# ZYNQ400-CONDIP.net
KiCad netlist of a schematic drawn in Altium Designer
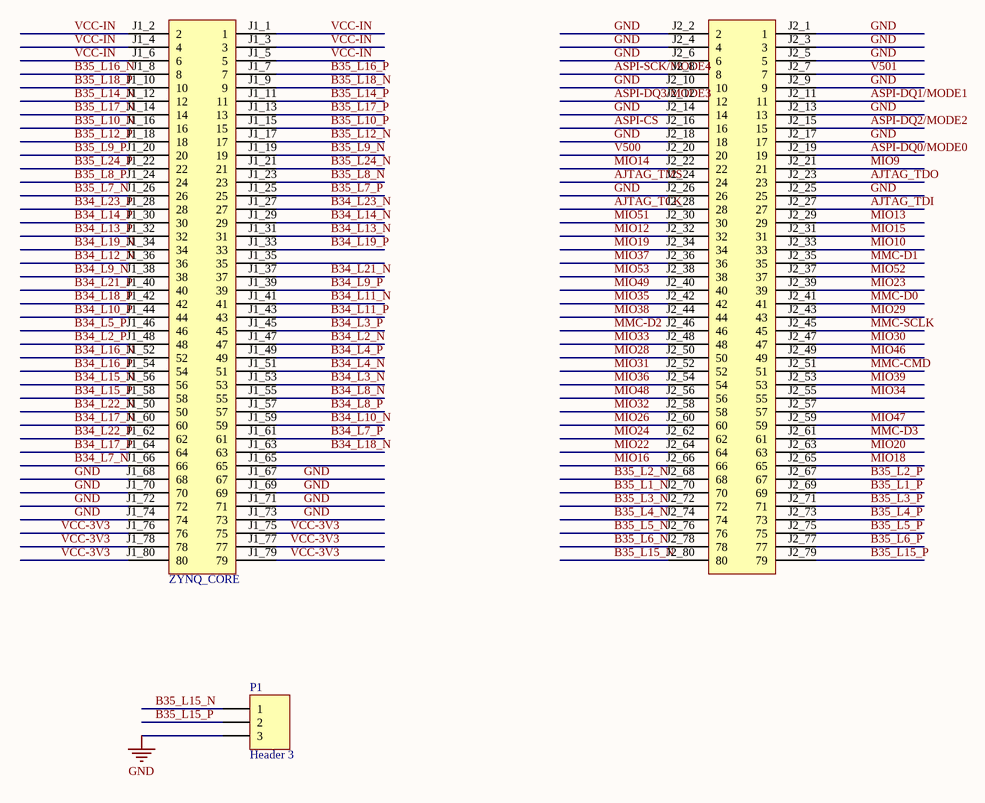
[diagram p0: ZYNQ400-CONDIP.SchDoc]

(export (version "E")
  (design (tool "Eeschema 10.0.6"))
  (components
    (comp (ref "M1")
      (value "ZYNQ_CORE")
      (footprint "ZYNQ7010&7020")
      (description "ZYNQ7010&7020 Core Board")
      (libsource (lib "ZYNQ领航者底板") (part "ZYNQ7010&7020"))
    )
    (comp (ref "P1")
      (value "Header 3")
      (footprint "HDR1X3")
      (description "Header, 3-Pin")
      (fields (field (name "PUBLISHER") "Altium Limited"))
      (libsource (lib "Miscellaneous Connectors") (part "Header 3"))
    )
  )
  (nets
    (net (code "1") (name "/AJTAG_TCK") (class "Default")
      (node (ref "M1") (pin "J2_28") (pinfunction "28_J2_28") (pintype "passive"))
    )
    (net (code "2") (name "/AJTAG_TDI") (class "Default")
      (node (ref "M1") (pin "J2_27") (pinfunction "27_J2_27") (pintype "passive"))
    )
    (net (code "3") (name "/AJTAG_TDO") (class "Default")
      (node (ref "M1") (pin "J2_23") (pinfunction "23_J2_23") (pintype "passive"))
    )
    (net (code "4") (name "/AJTAG_TMS") (class "Default")
      (node (ref "M1") (pin "J2_24") (pinfunction "24_J2_24") (pintype "passive"))
    )
    (net (code "5") (name "/ASPI-CS") (class "Default")
      (node (ref "M1") (pin "J2_16") (pinfunction "16_J2_16") (pintype "passive"))
    )
    (net (code "6") (name "/ASPI-DQ0{slash}MODE0") (class "Default")
      (node (ref "M1") (pin "J2_19") (pinfunction "19_J2_19") (pintype "passive"))
    )
    (net (code "7") (name "/ASPI-DQ1{slash}MODE1") (class "Default")
      (node (ref "M1") (pin "J2_11") (pinfunction "11_J2_11") (pintype "passive"))
    )
    (net (code "8") (name "/ASPI-DQ2{slash}MODE2") (class "Default")
      (node (ref "M1") (pin "J2_15") (pinfunction "15_J2_15") (pintype "passive"))
    )
    (net (code "9") (name "/ASPI-DQ3{slash}MODE3") (class "Default")
      (node (ref "M1") (pin "J2_12") (pinfunction "12_J2_12") (pintype "passive"))
    )
    (net (code "10") (name "/ASPI-SCK{slash}MODE4") (class "Default")
      (node (ref "M1") (pin "J2_8") (pinfunction "8_J2_8") (pintype "passive"))
    )
    (net (code "11") (name "/B34_L2_N") (class "Default")
      (node (ref "M1") (pin "J1_47") (pinfunction "47_J1_47") (pintype "passive"))
    )
    (net (code "12") (name "/B34_L2_P") (class "Default")
      (node (ref "M1") (pin "J1_48") (pinfunction "48_J1_48") (pintype "passive"))
    )
    (net (code "13") (name "/B34_L3_N") (class "Default")
      (node (ref "M1") (pin "J1_53") (pinfunction "53_J1_53") (pintype "passive"))
    )
    (net (code "14") (name "/B34_L3_P") (class "Default")
      (node (ref "M1") (pin "J1_45") (pinfunction "45_J1_45") (pintype "passive"))
    )
    (net (code "15") (name "/B34_L4_N") (class "Default")
      (node (ref "M1") (pin "J1_51") (pinfunction "51_J1_51") (pintype "passive"))
    )
    (net (code "16") (name "/B34_L4_P") (class "Default")
      (node (ref "M1") (pin "J1_49") (pinfunction "49_J1_49") (pintype "passive"))
    )
    (net (code "17") (name "/B34_L5_P") (class "Default")
      (node (ref "M1") (pin "J1_46") (pinfunction "46_J1_46") (pintype "passive"))
    )
    (net (code "18") (name "/B34_L7_N") (class "Default")
      (node (ref "M1") (pin "J1_66") (pinfunction "66_J1_66") (pintype "passive"))
    )
    (net (code "19") (name "/B34_L7_P") (class "Default")
      (node (ref "M1") (pin "J1_61") (pinfunction "61_J1_61") (pintype "passive"))
    )
    (net (code "20") (name "/B34_L8_N") (class "Default")
      (node (ref "M1") (pin "J1_55") (pinfunction "55_J1_55") (pintype "passive"))
    )
    (net (code "21") (name "/B34_L8_P") (class "Default")
      (node (ref "M1") (pin "J1_57") (pinfunction "57_J1_57") (pintype "passive"))
    )
    (net (code "22") (name "/B34_L9_N") (class "Default")
      (node (ref "M1") (pin "J1_38") (pinfunction "38_J1_38") (pintype "passive"))
    )
    (net (code "23") (name "/B34_L9_P") (class "Default")
      (node (ref "M1") (pin "J1_39") (pinfunction "39_J1_39") (pintype "passive"))
    )
    (net (code "24") (name "/B34_L10_N") (class "Default")
      (node (ref "M1") (pin "J1_59") (pinfunction "59_J1_59") (pintype "passive"))
    )
    (net (code "25") (name "/B34_L10_P") (class "Default")
      (node (ref "M1") (pin "J1_44") (pinfunction "44_J1_44") (pintype "passive"))
    )
    (net (code "26") (name "/B34_L11_N") (class "Default")
      (node (ref "M1") (pin "J1_41") (pinfunction "41_J1_41") (pintype "passive"))
    )
    (net (code "27") (name "/B34_L11_P") (class "Default")
      (node (ref "M1") (pin "J1_43") (pinfunction "43_J1_43") (pintype "passive"))
    )
    (net (code "28") (name "/B34_L12_N") (class "Default")
      (node (ref "M1") (pin "J1_36") (pinfunction "36_J1_36") (pintype "passive"))
    )
    (net (code "29") (name "/B34_L13_N") (class "Default")
      (node (ref "M1") (pin "J1_31") (pinfunction "31_J1_31") (pintype "passive"))
    )
    (net (code "30") (name "/B34_L13_P") (class "Default")
      (node (ref "M1") (pin "J1_32") (pinfunction "32_J1_32") (pintype "passive"))
    )
    (net (code "31") (name "/B34_L14_N") (class "Default")
      (node (ref "M1") (pin "J1_29") (pinfunction "29_J1_29") (pintype "passive"))
    )
    (net (code "32") (name "/B34_L14_P") (class "Default")
      (node (ref "M1") (pin "J1_30") (pinfunction "30_J1_30") (pintype "passive"))
    )
    (net (code "33") (name "/B34_L15_N") (class "Default")
      (node (ref "M1") (pin "J1_56") (pinfunction "56_J1_56") (pintype "passive"))
    )
    (net (code "34") (name "/B34_L15_P") (class "Default")
      (node (ref "M1") (pin "J1_58") (pinfunction "58_J1_58") (pintype "passive"))
    )
    (net (code "35") (name "/B34_L16_N") (class "Default")
      (node (ref "M1") (pin "J1_52") (pinfunction "52_J1_52") (pintype "passive"))
    )
    (net (code "36") (name "/B34_L16_P") (class "Default")
      (node (ref "M1") (pin "J1_54") (pinfunction "54_J1_54") (pintype "passive"))
    )
    (net (code "37") (name "/B34_L17_N") (class "Default")
      (node (ref "M1") (pin "J1_60") (pinfunction "60_J1_60") (pintype "passive"))
    )
    (net (code "38") (name "/B34_L17_P") (class "Default")
      (node (ref "M1") (pin "J1_64") (pinfunction "64_J1_64") (pintype "passive"))
    )
    (net (code "39") (name "/B34_L18_N") (class "Default")
      (node (ref "M1") (pin "J1_63") (pinfunction "63_J1_63") (pintype "passive"))
    )
    (net (code "40") (name "/B34_L18_P") (class "Default")
      (node (ref "M1") (pin "J1_42") (pinfunction "42_J1_42") (pintype "passive"))
    )
    (net (code "41") (name "/B34_L19_N") (class "Default")
      (node (ref "M1") (pin "J1_34") (pinfunction "34_J1_34") (pintype "passive"))
    )
    (net (code "42") (name "/B34_L19_P") (class "Default")
      (node (ref "M1") (pin "J1_33") (pinfunction "33_J1_33") (pintype "passive"))
    )
    (net (code "43") (name "/B34_L21_N") (class "Default")
      (node (ref "M1") (pin "J1_37") (pinfunction "37_J1_37") (pintype "passive"))
    )
    (net (code "44") (name "/B34_L21_P") (class "Default")
      (node (ref "M1") (pin "J1_40") (pinfunction "40_J1_40") (pintype "passive"))
    )
    (net (code "45") (name "/B34_L22_N") (class "Default")
      (node (ref "M1") (pin "J1_50") (pinfunction "50_J1_50") (pintype "passive"))
    )
    (net (code "46") (name "/B34_L22_P") (class "Default")
      (node (ref "M1") (pin "J1_62") (pinfunction "62_J1_62") (pintype "passive"))
    )
    (net (code "47") (name "/B34_L23_N") (class "Default")
      (node (ref "M1") (pin "J1_27") (pinfunction "27_J1_27") (pintype "passive"))
    )
    (net (code "48") (name "/B34_L23_P") (class "Default")
      (node (ref "M1") (pin "J1_28") (pinfunction "28_J1_28") (pintype "passive"))
    )
    (net (code "49") (name "/B35_L1_N") (class "Default")
      (node (ref "M1") (pin "J2_70") (pinfunction "70_J2_70") (pintype "passive"))
    )
    (net (code "50") (name "/B35_L1_P") (class "Default")
      (node (ref "M1") (pin "J2_69") (pinfunction "69_J2_69") (pintype "passive"))
    )
    (net (code "51") (name "/B35_L2_N") (class "Default")
      (node (ref "M1") (pin "J2_68") (pinfunction "68_J2_68") (pintype "passive"))
    )
    (net (code "52") (name "/B35_L2_P") (class "Default")
      (node (ref "M1") (pin "J2_67") (pinfunction "67_J2_67") (pintype "passive"))
    )
    (net (code "53") (name "/B35_L3_N") (class "Default")
      (node (ref "M1") (pin "J2_72") (pinfunction "72_J2_72") (pintype "passive"))
    )
    (net (code "54") (name "/B35_L3_P") (class "Default")
      (node (ref "M1") (pin "J2_71") (pinfunction "71_J2_71") (pintype "passive"))
    )
    (net (code "55") (name "/B35_L4_N") (class "Default")
      (node (ref "M1") (pin "J2_74") (pinfunction "74_J2_74") (pintype "passive"))
    )
    (net (code "56") (name "/B35_L4_P") (class "Default")
      (node (ref "M1") (pin "J2_73") (pinfunction "73_J2_73") (pintype "passive"))
    )
    (net (code "57") (name "/B35_L5_N") (class "Default")
      (node (ref "M1") (pin "J2_76") (pinfunction "76_J2_76") (pintype "passive"))
    )
    (net (code "58") (name "/B35_L5_P") (class "Default")
      (node (ref "M1") (pin "J2_75") (pinfunction "75_J2_75") (pintype "passive"))
    )
    (net (code "59") (name "/B35_L6_N") (class "Default")
      (node (ref "M1") (pin "J2_78") (pinfunction "78_J2_78") (pintype "passive"))
    )
    (net (code "60") (name "/B35_L6_P") (class "Default")
      (node (ref "M1") (pin "J2_77") (pinfunction "77_J2_77") (pintype "passive"))
    )
    (net (code "61") (name "/B35_L7_N") (class "Default")
      (node (ref "M1") (pin "J1_26") (pinfunction "26_J1_26") (pintype "passive"))
    )
    (net (code "62") (name "/B35_L7_P") (class "Default")
      (node (ref "M1") (pin "J1_25") (pinfunction "25_J1_25") (pintype "passive"))
    )
    (net (code "63") (name "/B35_L8_N") (class "Default")
      (node (ref "M1") (pin "J1_23") (pinfunction "23_J1_23") (pintype "passive"))
    )
    (net (code "64") (name "/B35_L8_P") (class "Default")
      (node (ref "M1") (pin "J1_24") (pinfunction "24_J1_24") (pintype "passive"))
    )
    (net (code "65") (name "/B35_L9_N") (class "Default")
      (node (ref "M1") (pin "J1_19") (pinfunction "19_J1_19") (pintype "passive"))
    )
    (net (code "66") (name "/B35_L9_P") (class "Default")
      (node (ref "M1") (pin "J1_20") (pinfunction "20_J1_20") (pintype "passive"))
    )
    (net (code "67") (name "/B35_L10_N") (class "Default")
      (node (ref "M1") (pin "J1_16") (pinfunction "16_J1_16") (pintype "passive"))
    )
    (net (code "68") (name "/B35_L10_P") (class "Default")
      (node (ref "M1") (pin "J1_15") (pinfunction "15_J1_15") (pintype "passive"))
    )
    (net (code "69") (name "/B35_L12_N") (class "Default")
      (node (ref "M1") (pin "J1_17") (pinfunction "17_J1_17") (pintype "passive"))
    )
    (net (code "70") (name "/B35_L12_P") (class "Default")
      (node (ref "M1") (pin "J1_18") (pinfunction "18_J1_18") (pintype "passive"))
    )
    (net (code "71") (name "/B35_L14_N") (class "Default")
      (node (ref "M1") (pin "J1_12") (pinfunction "12_J1_12") (pintype "passive"))
    )
    (net (code "72") (name "/B35_L14_P") (class "Default")
      (node (ref "M1") (pin "J1_11") (pinfunction "11_J1_11") (pintype "passive"))
    )
    (net (code "73") (name "/B35_L15_N") (class "Default")
      (node (ref "M1") (pin "J2_80") (pinfunction "80_J2_80") (pintype "passive"))
      (node (ref "P1") (pin "1") (pinfunction "1_1") (pintype "passive"))
    )
    (net (code "74") (name "/B35_L15_P") (class "Default")
      (node (ref "M1") (pin "J2_79") (pinfunction "79_J2_79") (pintype "passive"))
      (node (ref "P1") (pin "2") (pinfunction "2_2") (pintype "passive"))
    )
    (net (code "75") (name "/B35_L16_N") (class "Default")
      (node (ref "M1") (pin "J1_8") (pinfunction "8_J1_8") (pintype "passive"))
    )
    (net (code "76") (name "/B35_L16_P") (class "Default")
      (node (ref "M1") (pin "J1_7") (pinfunction "7_J1_7") (pintype "passive"))
    )
    (net (code "77") (name "/B35_L17_N") (class "Default")
      (node (ref "M1") (pin "J1_14") (pinfunction "14_J1_14") (pintype "passive"))
    )
    (net (code "78") (name "/B35_L17_P") (class "Default")
      (node (ref "M1") (pin "J1_13") (pinfunction "13_J1_13") (pintype "passive"))
    )
    (net (code "79") (name "/B35_L18_N") (class "Default")
      (node (ref "M1") (pin "J1_9") (pinfunction "9_J1_9") (pintype "passive"))
    )
    (net (code "80") (name "/B35_L18_P") (class "Default")
      (node (ref "M1") (pin "J1_10") (pinfunction "10_J1_10") (pintype "passive"))
    )
    (net (code "81") (name "/B35_L24_N") (class "Default")
      (node (ref "M1") (pin "J1_21") (pinfunction "21_J1_21") (pintype "passive"))
    )
    (net (code "82") (name "/B35_L24_P") (class "Default")
      (node (ref "M1") (pin "J1_22") (pinfunction "22_J1_22") (pintype "passive"))
    )
    (net (code "83") (name "/MIO9") (class "Default")
      (node (ref "M1") (pin "J2_21") (pinfunction "21_J2_21") (pintype "passive"))
    )
    (net (code "84") (name "/MIO10") (class "Default")
      (node (ref "M1") (pin "J2_33") (pinfunction "33_J2_33") (pintype "passive"))
    )
    (net (code "85") (name "/MIO12") (class "Default")
      (node (ref "M1") (pin "J2_32") (pinfunction "32_J2_32") (pintype "passive"))
    )
    (net (code "86") (name "/MIO13") (class "Default")
      (node (ref "M1") (pin "J2_29") (pinfunction "29_J2_29") (pintype "passive"))
    )
    (net (code "87") (name "/MIO14") (class "Default")
      (node (ref "M1") (pin "J2_22") (pinfunction "22_J2_22") (pintype "passive"))
    )
    (net (code "88") (name "/MIO15") (class "Default")
      (node (ref "M1") (pin "J2_31") (pinfunction "31_J2_31") (pintype "passive"))
    )
    (net (code "89") (name "/MIO16") (class "Default")
      (node (ref "M1") (pin "J2_66") (pinfunction "66_J2_66") (pintype "passive"))
    )
    (net (code "90") (name "/MIO18") (class "Default")
      (node (ref "M1") (pin "J2_65") (pinfunction "65_J2_65") (pintype "passive"))
    )
    (net (code "91") (name "/MIO19") (class "Default")
      (node (ref "M1") (pin "J2_34") (pinfunction "34_J2_34") (pintype "passive"))
    )
    (net (code "92") (name "/MIO20") (class "Default")
      (node (ref "M1") (pin "J2_63") (pinfunction "63_J2_63") (pintype "passive"))
    )
    (net (code "93") (name "/MIO22") (class "Default")
      (node (ref "M1") (pin "J2_64") (pinfunction "64_J2_64") (pintype "passive"))
    )
    (net (code "94") (name "/MIO23") (class "Default")
      (node (ref "M1") (pin "J2_39") (pinfunction "39_J2_39") (pintype "passive"))
    )
    (net (code "95") (name "/MIO24") (class "Default")
      (node (ref "M1") (pin "J2_62") (pinfunction "62_J2_62") (pintype "passive"))
    )
    (net (code "96") (name "/MIO26") (class "Default")
      (node (ref "M1") (pin "J2_60") (pinfunction "60_J2_60") (pintype "passive"))
    )
    (net (code "97") (name "/MIO28") (class "Default")
      (node (ref "M1") (pin "J2_50") (pinfunction "50_J2_50") (pintype "passive"))
    )
    (net (code "98") (name "/MIO29") (class "Default")
      (node (ref "M1") (pin "J2_43") (pinfunction "43_J2_43") (pintype "passive"))
    )
    (net (code "99") (name "/MIO30") (class "Default")
      (node (ref "M1") (pin "J2_47") (pinfunction "47_J2_47") (pintype "passive"))
    )
    (net (code "100") (name "/MIO31") (class "Default")
      (node (ref "M1") (pin "J2_52") (pinfunction "52_J2_52") (pintype "passive"))
    )
    (net (code "101") (name "/MIO32") (class "Default")
      (node (ref "M1") (pin "J2_58") (pinfunction "58_J2_58") (pintype "passive"))
    )
    (net (code "102") (name "/MIO33") (class "Default")
      (node (ref "M1") (pin "J2_48") (pinfunction "48_J2_48") (pintype "passive"))
    )
    (net (code "103") (name "/MIO34") (class "Default")
      (node (ref "M1") (pin "J2_55") (pinfunction "55_J2_55") (pintype "passive"))
    )
    (net (code "104") (name "/MIO35") (class "Default")
      (node (ref "M1") (pin "J2_42") (pinfunction "42_J2_42") (pintype "passive"))
    )
    (net (code "105") (name "/MIO36") (class "Default")
      (node (ref "M1") (pin "J2_54") (pinfunction "54_J2_54") (pintype "passive"))
    )
    (net (code "106") (name "/MIO37") (class "Default")
      (node (ref "M1") (pin "J2_36") (pinfunction "36_J2_36") (pintype "passive"))
    )
    (net (code "107") (name "/MIO38") (class "Default")
      (node (ref "M1") (pin "J2_44") (pinfunction "44_J2_44") (pintype "passive"))
    )
    (net (code "108") (name "/MIO39") (class "Default")
      (node (ref "M1") (pin "J2_53") (pinfunction "53_J2_53") (pintype "passive"))
    )
    (net (code "109") (name "/MIO46") (class "Default")
      (node (ref "M1") (pin "J2_49") (pinfunction "49_J2_49") (pintype "passive"))
    )
    (net (code "110") (name "/MIO47") (class "Default")
      (node (ref "M1") (pin "J2_59") (pinfunction "59_J2_59") (pintype "passive"))
    )
    (net (code "111") (name "/MIO48") (class "Default")
      (node (ref "M1") (pin "J2_56") (pinfunction "56_J2_56") (pintype "passive"))
    )
    (net (code "112") (name "/MIO49") (class "Default")
      (node (ref "M1") (pin "J2_40") (pinfunction "40_J2_40") (pintype "passive"))
    )
    (net (code "113") (name "/MIO51") (class "Default")
      (node (ref "M1") (pin "J2_30") (pinfunction "30_J2_30") (pintype "passive"))
    )
    (net (code "114") (name "/MIO52") (class "Default")
      (node (ref "M1") (pin "J2_37") (pinfunction "37_J2_37") (pintype "passive"))
    )
    (net (code "115") (name "/MIO53") (class "Default")
      (node (ref "M1") (pin "J2_38") (pinfunction "38_J2_38") (pintype "passive"))
    )
    (net (code "116") (name "/MMC-CMD") (class "Default")
      (node (ref "M1") (pin "J2_51") (pinfunction "51_J2_51") (pintype "passive"))
    )
    (net (code "117") (name "/MMC-D0") (class "Default")
      (node (ref "M1") (pin "J2_41") (pinfunction "41_J2_41") (pintype "passive"))
    )
    (net (code "118") (name "/MMC-D1") (class "Default")
      (node (ref "M1") (pin "J2_35") (pinfunction "35_J2_35") (pintype "passive"))
    )
    (net (code "119") (name "/MMC-D2") (class "Default")
      (node (ref "M1") (pin "J2_46") (pinfunction "46_J2_46") (pintype "passive"))
    )
    (net (code "120") (name "/MMC-D3") (class "Default")
      (node (ref "M1") (pin "J2_61") (pinfunction "61_J2_61") (pintype "passive"))
    )
    (net (code "121") (name "/MMC-SCLK") (class "Default")
      (node (ref "M1") (pin "J2_45") (pinfunction "45_J2_45") (pintype "passive"))
    )
    (net (code "122") (name "/V500") (class "Default")
      (node (ref "M1") (pin "J2_20") (pinfunction "20_J2_20") (pintype "passive"))
    )
    (net (code "123") (name "/V501") (class "Default")
      (node (ref "M1") (pin "J2_7") (pinfunction "7_J2_7") (pintype "passive"))
    )
    (net (code "124") (name "/VCC-3V3") (class "Default")
      (node (ref "M1") (pin "J1_75") (pinfunction "75_J1_75") (pintype "passive"))
      (node (ref "M1") (pin "J1_76") (pinfunction "76_J1_76") (pintype "passive"))
      (node (ref "M1") (pin "J1_77") (pinfunction "77_J1_77") (pintype "passive"))
      (node (ref "M1") (pin "J1_78") (pinfunction "78_J1_78") (pintype "passive"))
      (node (ref "M1") (pin "J1_79") (pinfunction "79_J1_79") (pintype "passive"))
      (node (ref "M1") (pin "J1_80") (pinfunction "80_J1_80") (pintype "passive"))
    )
    (net (code "125") (name "/VCC-IN") (class "Default")
      (node (ref "M1") (pin "J1_1") (pinfunction "1_J1_1") (pintype "passive"))
      (node (ref "M1") (pin "J1_2") (pinfunction "2_J1_2") (pintype "passive"))
      (node (ref "M1") (pin "J1_3") (pinfunction "3_J1_3") (pintype "passive"))
      (node (ref "M1") (pin "J1_4") (pinfunction "4_J1_4") (pintype "passive"))
      (node (ref "M1") (pin "J1_5") (pinfunction "5_J1_5") (pintype "passive"))
      (node (ref "M1") (pin "J1_6") (pinfunction "6_J1_6") (pintype "passive"))
    )
    (net (code "126") (name "GND") (class "Default")
      (node (ref "M1") (pin "J1_67") (pinfunction "67_J1_67") (pintype "passive"))
      (node (ref "M1") (pin "J1_68") (pinfunction "68_J1_68") (pintype "passive"))
      (node (ref "M1") (pin "J1_69") (pinfunction "69_J1_69") (pintype "passive"))
      (node (ref "M1") (pin "J1_70") (pinfunction "70_J1_70") (pintype "passive"))
      (node (ref "M1") (pin "J1_71") (pinfunction "71_J1_71") (pintype "passive"))
      (node (ref "M1") (pin "J1_72") (pinfunction "72_J1_72") (pintype "passive"))
      (node (ref "M1") (pin "J1_73") (pinfunction "73_J1_73") (pintype "passive"))
      (node (ref "M1") (pin "J1_74") (pinfunction "74_J1_74") (pintype "passive"))
      (node (ref "M1") (pin "J2_1") (pinfunction "1_J2_1") (pintype "passive"))
      (node (ref "M1") (pin "J2_10") (pinfunction "10_J2_10") (pintype "passive"))
      (node (ref "M1") (pin "J2_13") (pinfunction "13_J2_13") (pintype "passive"))
      (node (ref "M1") (pin "J2_14") (pinfunction "14_J2_14") (pintype "passive"))
      (node (ref "M1") (pin "J2_17") (pinfunction "17_J2_17") (pintype "passive"))
      (node (ref "M1") (pin "J2_18") (pinfunction "18_J2_18") (pintype "passive"))
      (node (ref "M1") (pin "J2_2") (pinfunction "2_J2_2") (pintype "passive"))
      (node (ref "M1") (pin "J2_25") (pinfunction "25_J2_25") (pintype "passive"))
      (node (ref "M1") (pin "J2_26") (pinfunction "26_J2_26") (pintype "passive"))
      (node (ref "M1") (pin "J2_3") (pinfunction "3_J2_3") (pintype "passive"))
      (node (ref "M1") (pin "J2_4") (pinfunction "4_J2_4") (pintype "passive"))
      (node (ref "M1") (pin "J2_5") (pinfunction "5_J2_5") (pintype "passive"))
      (node (ref "M1") (pin "J2_6") (pinfunction "6_J2_6") (pintype "passive"))
      (node (ref "M1") (pin "J2_9") (pinfunction "9_J2_9") (pintype "passive"))
      (node (ref "P1") (pin "3") (pinfunction "3_3") (pintype "passive"))
    )
    (net (code "127") (name "unconnected-(M1-35-PadJ1_35)") (class "Default")
      (node (ref "M1") (pin "J1_35") (pinfunction "35_J1_35") (pintype "passive"))
    )
    (net (code "128") (name "unconnected-(M1-57-PadJ2_57)") (class "Default")
      (node (ref "M1") (pin "J2_57") (pinfunction "57_J2_57") (pintype "passive"))
    )
    (net (code "129") (name "unconnected-(M1-65-PadJ1_65)") (class "Default")
      (node (ref "M1") (pin "J1_65") (pinfunction "65_J1_65") (pintype "passive"))
    )
  )
)
